# STM32H743VGT6.net
KiCad netlist of a schematic drawn in Altium Designer
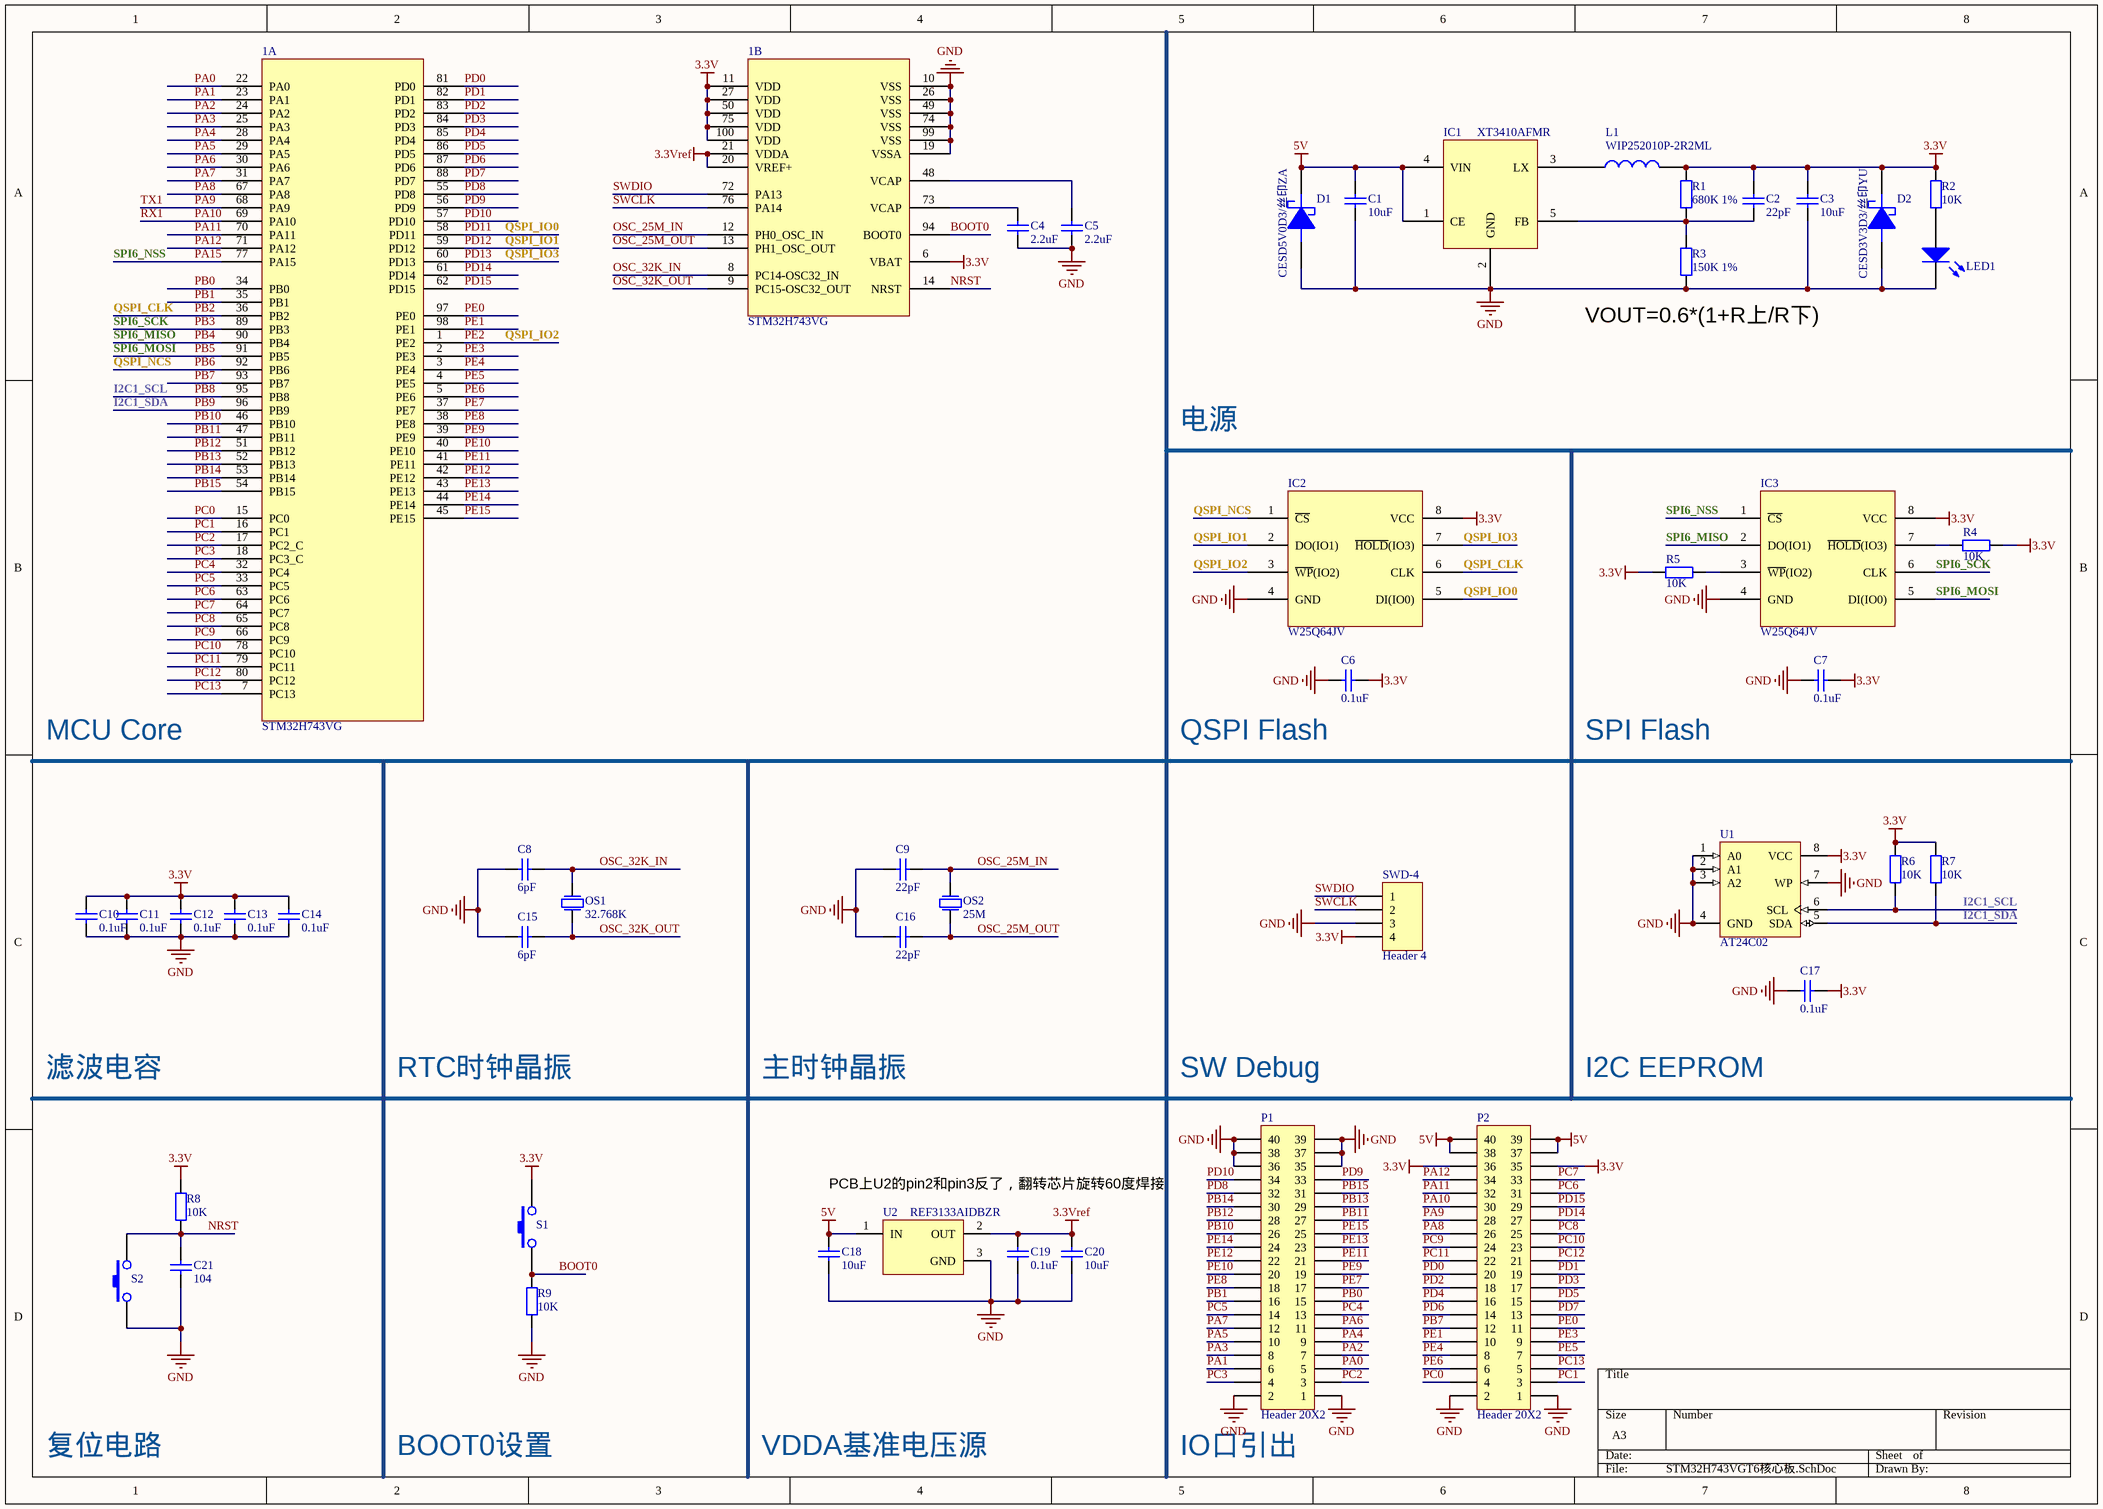
[diagram p0: STM32H743VGT6核心板.SchDoc]

(export (version "E")
  (design (tool "Eeschema 10.0.6"))
  (components
    (comp (ref "1")
      (value "STM32H743VG")
      (footprint "F-QFP14x14-G100/P.5N")
      (libsource (lib "反客STM32H743VGT6核心板零散元件") (part "STM32H743VG"))
    )
    (comp (ref "C1")
      (value "10uF")
      (footprint "C 0603_M")
      (libsource (lib "反客STM32H743VGT6核心板零散元件") (part "Cap1_3"))
    )
    (comp (ref "C2")
      (value "22pF")
      (footprint "C 0603_M")
      (libsource (lib "反客STM32H743VGT6核心板零散元件") (part "Cap1_1"))
    )
    (comp (ref "C3")
      (value "10uF")
      (footprint "C 0603_M")
      (libsource (lib "反客STM32H743VGT6核心板零散元件") (part "Cap1_3"))
    )
    (comp (ref "C4")
      (value "2.2uF")
      (footprint "C 0603_M")
      (libsource (lib "反客STM32H743VGT6核心板零散元件") (part "Cap1_4"))
    )
    (comp (ref "C5")
      (value "2.2uF")
      (footprint "C 0603_M")
      (libsource (lib "反客STM32H743VGT6核心板零散元件") (part "Cap1_4"))
    )
    (comp (ref "C6")
      (value "0.1uF")
      (footprint "C 0603_M")
      (libsource (lib "反客STM32H743VGT6核心板零散元件") (part "Cap1"))
    )
    (comp (ref "C7")
      (value "0.1uF")
      (footprint "C 0603_M")
      (libsource (lib "反客STM32H743VGT6核心板零散元件") (part "Cap1"))
    )
    (comp (ref "C8") (value "6pF") (footprint "C 0603_M") (libsource (lib "零散元件库") (part "Cap1")))
    (comp (ref "C9") (value "22pF") (footprint "C 0603_M") (libsource (lib "零散元件库") (part "Cap1")))
    (comp (ref "C10")
      (value "0.1uF")
      (footprint "C 0603_M")
      (libsource (lib "反客STM32H743VGT6核心板零散元件") (part "Cap1"))
    )
    (comp (ref "C11")
      (value "0.1uF")
      (footprint "C 0603_M")
      (libsource (lib "反客STM32H743VGT6核心板零散元件") (part "Cap1"))
    )
    (comp (ref "C12")
      (value "0.1uF")
      (footprint "C 0603_M")
      (libsource (lib "反客STM32H743VGT6核心板零散元件") (part "Cap1"))
    )
    (comp (ref "C13")
      (value "0.1uF")
      (footprint "C 0603_M")
      (libsource (lib "反客STM32H743VGT6核心板零散元件") (part "Cap1"))
    )
    (comp (ref "C14")
      (value "0.1uF")
      (footprint "C 0603_M")
      (libsource (lib "反客STM32H743VGT6核心板零散元件") (part "Cap1"))
    )
    (comp (ref "C15") (value "6pF") (footprint "C 0603_M") (libsource (lib "零散元件库") (part "Cap1")))
    (comp (ref "C16") (value "22pF") (footprint "C 0603_M") (libsource (lib "零散元件库") (part "Cap1")))
    (comp (ref "C17")
      (value "0.1uF")
      (footprint "C 0603_M")
      (libsource (lib "反客STM32H743VGT6核心板零散元件") (part "Cap1"))
    )
    (comp (ref "C18")
      (value "10uF")
      (footprint "C 0603_M")
      (libsource (lib "反客STM32H743VGT6核心板零散元件") (part "Cap1_3"))
    )
    (comp (ref "C19")
      (value "0.1uF")
      (footprint "C 0603_M")
      (libsource (lib "反客STM32H743VGT6核心板零散元件") (part "Cap1"))
    )
    (comp (ref "C20")
      (value "10uF")
      (footprint "C 0603_M")
      (libsource (lib "反客STM32H743VGT6核心板零散元件") (part "Cap1_3"))
    )
    (comp (ref "C21") (value "104") (footprint "C 0603_M") (libsource (lib "零散元件库") (part "Cap1")))
    (comp (ref "D1")
      (value "CESD5V0D3/丝印ZA")
      (footprint "SOD323")
      (libsource (lib "反客STM32H743VGT6核心板零散元件") (part "TVS"))
    )
    (comp (ref "D2")
      (value "CESD3V3D3/丝印YU")
      (footprint "SOD323")
      (libsource (lib "反客STM32H743VGT6核心板零散元件") (part "TVS_1"))
    )
    (comp (ref "IC1")
      (value "XT3410AFMR")
      (footprint "SOT23-5P")
      (libsource (lib "反客STM32H743VGT6核心板零散元件") (part "XT3410AFMR"))
    )
    (comp (ref "IC2")
      (value "W25Q64JV")
      (footprint "SOIC-W-8")
      (libsource (lib "反客STM32H743VGT6核心板零散元件") (part "W25QXX_FLASH"))
    )
    (comp (ref "IC3")
      (value "W25Q64JV")
      (footprint "SOIC-W-8")
      (libsource (lib "反客STM32H743VGT6核心板零散元件") (part "W25QXX_FLASH"))
    )
    (comp (ref "L1")
      (value "WIP252010P-2R2ML")
      (footprint "电感2520X10N")
      (libsource (lib "反客STM32H743VGT6核心板零散元件") (part "电感_1"))
    )
    (comp (ref "LED1")
      (value "LED")
      (footprint "LED 0603W")
      (libsource (lib "反客STM32H743VGT6核心板零散元件") (part "LED"))
    )
    (comp (ref "OS1")
      (value "32.768K")
      (footprint "R 0805_M")
      (fields (field (name "VAULE") "32.768K"))
      (libsource (lib "零散元件库") (part "晶振"))
    )
    (comp (ref "OS2")
      (value "25M")
      (footprint "3225")
      (fields (field (name "VAULE") "25M"))
      (libsource (lib "反客STM32H743VGT6核心板零散元件") (part "晶振"))
    )
    (comp (ref "P1")
      (value "Header 20X2")
      (footprint "HDR-SMD_40P-P1.27-V-M-R2-C20-LS5.3")
      (description "Header, 20-Pin, Dual row")
      (fields (field (name "PUBLISHER") "Altium Limited"))
      (libsource (lib "反客STM32H743VGT6核心板零散元件") (part "Header 20X2"))
    )
    (comp (ref "P2")
      (value "Header 20X2")
      (footprint "HDR-SMD_40P-P1.27-V-M-R2-C20-LS5.3")
      (description "Header, 20-Pin, Dual row")
      (fields (field (name "PUBLISHER") "Altium Limited"))
      (libsource (lib "反客STM32H743VGT6核心板零散元件") (part "Header 20X2"))
    )
    (comp (ref "R1")
      (value "680K 1%")
      (footprint "R 0603_M")
      (libsource (lib "反客STM32H743VGT6核心板零散元件") (part "Res_5"))
    )
    (comp (ref "R2")
      (value "10K")
      (footprint "R 0603_M")
      (libsource (lib "反客STM32H743VGT6核心板零散元件") (part "Res"))
    )
    (comp (ref "R3")
      (value "150K 1%")
      (footprint "R 0603_M")
      (libsource (lib "反客STM32H743VGT6核心板零散元件") (part "Res_6"))
    )
    (comp (ref "R4")
      (value "10K")
      (footprint "R 0603_M")
      (libsource (lib "反客STM32H743VGT6核心板零散元件") (part "Res_1"))
    )
    (comp (ref "R5")
      (value "10K")
      (footprint "R 0603_M")
      (libsource (lib "反客STM32H743VGT6核心板零散元件") (part "Res_1"))
    )
    (comp (ref "R6") (value "10K") (footprint "R 0603_M") (libsource (lib "") (part "Res_1_1")))
    (comp (ref "R7") (value "10K") (footprint "R 0603_M") (libsource (lib "") (part "Res_1_1")))
    (comp (ref "R8") (value "10K") (footprint "R 0603_M") (libsource (lib "零散元件库") (part "Res")))
    (comp (ref "R9") (value "10K") (footprint "R 0603_M") (libsource (lib "零散元件库") (part "Res")))
    (comp (ref "S1") (value "KEY") (footprint "SWT3*4") (libsource (lib "CCDXPLIB") (part "KEY")))
    (comp (ref "S2") (value "KEY") (footprint "SWT3*4") (libsource (lib "CCDXPLIB") (part "KEY")))
    (comp (ref "SWD-4")
      (value "Header 4")
      (footprint "PH2.0-WI-4P")
      (description "Header, 4-Pin")
      (fields (field (name "PUBLISHER") "Altium Limited"))
      (libsource (lib "Miscellaneous Connectors") (part "Header 4"))
    )
    (comp (ref "U1")
      (value "AT24C02")
      (footprint "8S1_N")
      (libsource (lib "Atmel Serial EEPROM") (part "AT24C02BN-SP25-B"))
    )
    (comp (ref "U2")
      (value "REF3133AIDBZR")
      (footprint "SOT23")
      (fields (field (name "MANUFACTURER") "Texas Instruments"))
      (libsource (lib "TI Power Management Series Voltage Reference") (part "REF3133AIDBZR"))
    )
  )
  (nets
    (net (code "1") (name "/BOOT0") (class "Default")
      (node (ref "1") (pin "94") (pinfunction "BOOT0_94") (pintype "passive"))
      (node (ref "R9") (pin "2") (pinfunction "2_2") (pintype "passive"))
      (node (ref "S1") (pin "1") (pinfunction "1_1") (pintype "passive"))
    )
    (net (code "2") (name "/I2C1_SCL") (class "Default")
      (node (ref "1") (pin "95") (pinfunction "PB8_95") (pintype "passive"))
      (node (ref "R6") (pin "1") (pinfunction "1_1") (pintype "passive"))
      (node (ref "U1") (pin "6") (pinfunction "SCL_6") (pintype "input"))
    )
    (net (code "3") (name "/I2C1_SDA") (class "Default")
      (node (ref "1") (pin "96") (pinfunction "PB9_96") (pintype "passive"))
      (node (ref "R7") (pin "1") (pinfunction "1_1") (pintype "passive"))
      (node (ref "U1") (pin "5") (pinfunction "SDA_5") (pintype "bidirectional"))
    )
    (net (code "4") (name "/NRST") (class "Default")
      (node (ref "1") (pin "14") (pinfunction "NRST_14") (pintype "passive"))
      (node (ref "C21") (pin "2") (pinfunction "2_2") (pintype "passive"))
      (node (ref "R8") (pin "1") (pinfunction "1_1") (pintype "passive"))
      (node (ref "S2") (pin "2") (pinfunction "2_2") (pintype "passive"))
    )
    (net (code "5") (name "/OSC_25M_IN") (class "Default")
      (node (ref "1") (pin "12") (pinfunction "PH0_OSC_IN_12") (pintype "passive"))
      (node (ref "C9") (pin "1") (pinfunction "1_1") (pintype "passive"))
      (node (ref "OS2") (pin "1") (pinfunction "P1_1") (pintype "passive"))
    )
    (net (code "6") (name "/OSC_25M_OUT") (class "Default")
      (node (ref "1") (pin "13") (pinfunction "PH1_OSC_OUT_13") (pintype "passive"))
      (node (ref "C16") (pin "1") (pinfunction "1_1") (pintype "passive"))
      (node (ref "OS2") (pin "2") (pinfunction "P2_2") (pintype "passive"))
    )
    (net (code "7") (name "/OSC_32K_IN") (class "Default")
      (node (ref "1") (pin "8") (pinfunction "PC14-OSC32_IN_8") (pintype "passive"))
      (node (ref "C8") (pin "1") (pinfunction "1_1") (pintype "passive"))
      (node (ref "OS1") (pin "1") (pinfunction "P1_1") (pintype "passive"))
    )
    (net (code "8") (name "/OSC_32K_OUT") (class "Default")
      (node (ref "1") (pin "9") (pinfunction "PC15-OSC32_OUT_9") (pintype "passive"))
      (node (ref "C15") (pin "1") (pinfunction "1_1") (pintype "passive"))
      (node (ref "OS1") (pin "2") (pinfunction "P2_2") (pintype "passive"))
    )
    (net (code "9") (name "/PA0") (class "Default")
      (node (ref "1") (pin "22") (pinfunction "PA0_22") (pintype "passive"))
      (node (ref "P1") (pin "5") (pinfunction "5_5") (pintype "passive"))
    )
    (net (code "10") (name "/PA1") (class "Default")
      (node (ref "1") (pin "23") (pinfunction "PA1_23") (pintype "passive"))
      (node (ref "P1") (pin "6") (pinfunction "6_6") (pintype "passive"))
    )
    (net (code "11") (name "/PA2") (class "Default")
      (node (ref "1") (pin "24") (pinfunction "PA2_24") (pintype "passive"))
      (node (ref "P1") (pin "7") (pinfunction "7_7") (pintype "passive"))
    )
    (net (code "12") (name "/PA3") (class "Default")
      (node (ref "1") (pin "25") (pinfunction "PA3_25") (pintype "passive"))
      (node (ref "P1") (pin "8") (pinfunction "8_8") (pintype "passive"))
    )
    (net (code "13") (name "/PA4") (class "Default")
      (node (ref "1") (pin "28") (pinfunction "PA4_28") (pintype "passive"))
      (node (ref "P1") (pin "9") (pinfunction "9_9") (pintype "passive"))
    )
    (net (code "14") (name "/PA5") (class "Default")
      (node (ref "1") (pin "29") (pinfunction "PA5_29") (pintype "passive"))
      (node (ref "P1") (pin "10") (pinfunction "10_10") (pintype "passive"))
    )
    (net (code "15") (name "/PA6") (class "Default")
      (node (ref "1") (pin "30") (pinfunction "PA6_30") (pintype "passive"))
      (node (ref "P1") (pin "11") (pinfunction "11_11") (pintype "passive"))
    )
    (net (code "16") (name "/PA7") (class "Default")
      (node (ref "1") (pin "31") (pinfunction "PA7_31") (pintype "passive"))
      (node (ref "P1") (pin "12") (pinfunction "12_12") (pintype "passive"))
    )
    (net (code "17") (name "/PA8") (class "Default")
      (node (ref "1") (pin "67") (pinfunction "PA8_67") (pintype "passive"))
      (node (ref "P2") (pin "26") (pinfunction "26_26") (pintype "passive"))
    )
    (net (code "18") (name "/PA9") (class "Default")
      (node (ref "1") (pin "68") (pinfunction "PA9_68") (pintype "passive"))
      (node (ref "P2") (pin "28") (pinfunction "28_28") (pintype "passive"))
    )
    (net (code "19") (name "/PA10") (class "Default")
      (node (ref "1") (pin "69") (pinfunction "PA10_69") (pintype "passive"))
      (node (ref "P2") (pin "30") (pinfunction "30_30") (pintype "passive"))
    )
    (net (code "20") (name "/PA11") (class "Default")
      (node (ref "1") (pin "70") (pinfunction "PA11_70") (pintype "passive"))
      (node (ref "P2") (pin "32") (pinfunction "32_32") (pintype "passive"))
    )
    (net (code "21") (name "/PA12") (class "Default")
      (node (ref "1") (pin "71") (pinfunction "PA12_71") (pintype "passive"))
      (node (ref "P2") (pin "34") (pinfunction "34_34") (pintype "passive"))
    )
    (net (code "22") (name "/PA15") (class "Default")
      (node (ref "1") (pin "77") (pinfunction "PA15_77") (pintype "passive"))
      (node (ref "IC3") (pin "1") (pinfunction "~{CS}_1") (pintype "passive"))
    )
    (net (code "23") (name "/PB0") (class "Default")
      (node (ref "1") (pin "34") (pinfunction "PB0_34") (pintype "passive"))
      (node (ref "P1") (pin "15") (pinfunction "15_15") (pintype "passive"))
    )
    (net (code "24") (name "/PB1") (class "Default")
      (node (ref "1") (pin "35") (pinfunction "PB1_35") (pintype "passive"))
      (node (ref "P1") (pin "16") (pinfunction "16_16") (pintype "passive"))
    )
    (net (code "25") (name "/PB2") (class "Default")
      (node (ref "1") (pin "36") (pinfunction "PB2_36") (pintype "passive"))
      (node (ref "IC2") (pin "6") (pinfunction "CLK_6") (pintype "passive"))
    )
    (net (code "26") (name "/PB3") (class "Default")
      (node (ref "1") (pin "89") (pinfunction "PB3_89") (pintype "passive"))
      (node (ref "IC3") (pin "6") (pinfunction "CLK_6") (pintype "passive"))
    )
    (net (code "27") (name "/PB4") (class "Default")
      (node (ref "1") (pin "90") (pinfunction "PB4_90") (pintype "passive"))
      (node (ref "IC3") (pin "2") (pinfunction "DO(IO1)_2") (pintype "passive"))
    )
    (net (code "28") (name "/PB5") (class "Default")
      (node (ref "1") (pin "91") (pinfunction "PB5_91") (pintype "passive"))
      (node (ref "IC3") (pin "5") (pinfunction "DI(IO0)_5") (pintype "passive"))
    )
    (net (code "29") (name "/PB6") (class "Default")
      (node (ref "1") (pin "92") (pinfunction "PB6_92") (pintype "passive"))
      (node (ref "IC2") (pin "1") (pinfunction "~{CS}_1") (pintype "passive"))
    )
    (net (code "30") (name "/PB7") (class "Default")
      (node (ref "1") (pin "93") (pinfunction "PB7_93") (pintype "passive"))
      (node (ref "P2") (pin "12") (pinfunction "12_12") (pintype "passive"))
    )
    (net (code "31") (name "/PB10") (class "Default")
      (node (ref "1") (pin "46") (pinfunction "PB10_46") (pintype "passive"))
      (node (ref "P1") (pin "26") (pinfunction "26_26") (pintype "passive"))
    )
    (net (code "32") (name "/PB11") (class "Default")
      (node (ref "1") (pin "47") (pinfunction "PB11_47") (pintype "passive"))
      (node (ref "P1") (pin "27") (pinfunction "27_27") (pintype "passive"))
    )
    (net (code "33") (name "/PB12") (class "Default")
      (node (ref "1") (pin "51") (pinfunction "PB12_51") (pintype "passive"))
      (node (ref "P1") (pin "28") (pinfunction "28_28") (pintype "passive"))
    )
    (net (code "34") (name "/PB13") (class "Default")
      (node (ref "1") (pin "52") (pinfunction "PB13_52") (pintype "passive"))
      (node (ref "P1") (pin "29") (pinfunction "29_29") (pintype "passive"))
    )
    (net (code "35") (name "/PB14") (class "Default")
      (node (ref "1") (pin "53") (pinfunction "PB14_53") (pintype "passive"))
      (node (ref "P1") (pin "30") (pinfunction "30_30") (pintype "passive"))
    )
    (net (code "36") (name "/PB15") (class "Default")
      (node (ref "1") (pin "54") (pinfunction "PB15_54") (pintype "passive"))
      (node (ref "P1") (pin "31") (pinfunction "31_31") (pintype "passive"))
    )
    (net (code "37") (name "/PC0") (class "Default")
      (node (ref "1") (pin "15") (pinfunction "PC0_15") (pintype "passive"))
      (node (ref "P2") (pin "4") (pinfunction "4_4") (pintype "passive"))
    )
    (net (code "38") (name "/PC1") (class "Default")
      (node (ref "1") (pin "16") (pinfunction "PC1_16") (pintype "passive"))
      (node (ref "P2") (pin "3") (pinfunction "3_3") (pintype "passive"))
    )
    (net (code "39") (name "/PC2") (class "Default")
      (node (ref "1") (pin "17") (pinfunction "PC2_C_17") (pintype "passive"))
      (node (ref "P1") (pin "3") (pinfunction "3_3") (pintype "passive"))
    )
    (net (code "40") (name "/PC3") (class "Default")
      (node (ref "1") (pin "18") (pinfunction "PC3_C_18") (pintype "passive"))
      (node (ref "P1") (pin "4") (pinfunction "4_4") (pintype "passive"))
    )
    (net (code "41") (name "/PC4") (class "Default")
      (node (ref "1") (pin "32") (pinfunction "PC4_32") (pintype "passive"))
      (node (ref "P1") (pin "13") (pinfunction "13_13") (pintype "passive"))
    )
    (net (code "42") (name "/PC5") (class "Default")
      (node (ref "1") (pin "33") (pinfunction "PC5_33") (pintype "passive"))
      (node (ref "P1") (pin "14") (pinfunction "14_14") (pintype "passive"))
    )
    (net (code "43") (name "/PC6") (class "Default")
      (node (ref "1") (pin "63") (pinfunction "PC6_63") (pintype "passive"))
      (node (ref "P2") (pin "31") (pinfunction "31_31") (pintype "passive"))
    )
    (net (code "44") (name "/PC7") (class "Default")
      (node (ref "1") (pin "64") (pinfunction "PC7_64") (pintype "passive"))
      (node (ref "P2") (pin "33") (pinfunction "33_33") (pintype "passive"))
    )
    (net (code "45") (name "/PC8") (class "Default")
      (node (ref "1") (pin "65") (pinfunction "PC8_65") (pintype "passive"))
      (node (ref "P2") (pin "25") (pinfunction "25_25") (pintype "passive"))
    )
    (net (code "46") (name "/PC9") (class "Default")
      (node (ref "1") (pin "66") (pinfunction "PC9_66") (pintype "passive"))
      (node (ref "P2") (pin "24") (pinfunction "24_24") (pintype "passive"))
    )
    (net (code "47") (name "/PC10") (class "Default")
      (node (ref "1") (pin "78") (pinfunction "PC10_78") (pintype "passive"))
      (node (ref "P2") (pin "23") (pinfunction "23_23") (pintype "passive"))
    )
    (net (code "48") (name "/PC11") (class "Default")
      (node (ref "1") (pin "79") (pinfunction "PC11_79") (pintype "passive"))
      (node (ref "P2") (pin "22") (pinfunction "22_22") (pintype "passive"))
    )
    (net (code "49") (name "/PC12") (class "Default")
      (node (ref "1") (pin "80") (pinfunction "PC12_80") (pintype "passive"))
      (node (ref "P2") (pin "21") (pinfunction "21_21") (pintype "passive"))
    )
    (net (code "50") (name "/PC13") (class "Default")
      (node (ref "1") (pin "7") (pinfunction "PC13_7") (pintype "passive"))
      (node (ref "P2") (pin "5") (pinfunction "5_5") (pintype "passive"))
    )
    (net (code "51") (name "/PD0") (class "Default")
      (node (ref "1") (pin "81") (pinfunction "PD0_81") (pintype "passive"))
      (node (ref "P2") (pin "20") (pinfunction "20_20") (pintype "passive"))
    )
    (net (code "52") (name "/PD1") (class "Default")
      (node (ref "1") (pin "82") (pinfunction "PD1_82") (pintype "passive"))
      (node (ref "P2") (pin "19") (pinfunction "19_19") (pintype "passive"))
    )
    (net (code "53") (name "/PD2") (class "Default")
      (node (ref "1") (pin "83") (pinfunction "PD2_83") (pintype "passive"))
      (node (ref "P2") (pin "18") (pinfunction "18_18") (pintype "passive"))
    )
    (net (code "54") (name "/PD3") (class "Default")
      (node (ref "1") (pin "84") (pinfunction "PD3_84") (pintype "passive"))
      (node (ref "P2") (pin "17") (pinfunction "17_17") (pintype "passive"))
    )
    (net (code "55") (name "/PD4") (class "Default")
      (node (ref "1") (pin "85") (pinfunction "PD4_85") (pintype "passive"))
      (node (ref "P2") (pin "16") (pinfunction "16_16") (pintype "passive"))
    )
    (net (code "56") (name "/PD5") (class "Default")
      (node (ref "1") (pin "86") (pinfunction "PD5_86") (pintype "passive"))
      (node (ref "P2") (pin "15") (pinfunction "15_15") (pintype "passive"))
    )
    (net (code "57") (name "/PD6") (class "Default")
      (node (ref "1") (pin "87") (pinfunction "PD6_87") (pintype "passive"))
      (node (ref "P2") (pin "14") (pinfunction "14_14") (pintype "passive"))
    )
    (net (code "58") (name "/PD7") (class "Default")
      (node (ref "1") (pin "88") (pinfunction "PD7_88") (pintype "passive"))
      (node (ref "P2") (pin "13") (pinfunction "13_13") (pintype "passive"))
    )
    (net (code "59") (name "/PD8") (class "Default")
      (node (ref "1") (pin "55") (pinfunction "PD8_55") (pintype "passive"))
      (node (ref "P1") (pin "32") (pinfunction "32_32") (pintype "passive"))
    )
    (net (code "60") (name "/PD9") (class "Default")
      (node (ref "1") (pin "56") (pinfunction "PD9_56") (pintype "passive"))
      (node (ref "P1") (pin "33") (pinfunction "33_33") (pintype "passive"))
    )
    (net (code "61") (name "/PD10") (class "Default")
      (node (ref "1") (pin "57") (pinfunction "PD10_57") (pintype "passive"))
      (node (ref "P1") (pin "34") (pinfunction "34_34") (pintype "passive"))
    )
    (net (code "62") (name "/PD11") (class "Default")
      (node (ref "1") (pin "58") (pinfunction "PD11_58") (pintype "passive"))
      (node (ref "IC2") (pin "5") (pinfunction "DI(IO0)_5") (pintype "passive"))
    )
    (net (code "63") (name "/PD12") (class "Default")
      (node (ref "1") (pin "59") (pinfunction "PD12_59") (pintype "passive"))
      (node (ref "IC2") (pin "2") (pinfunction "DO(IO1)_2") (pintype "passive"))
    )
    (net (code "64") (name "/PD13") (class "Default")
      (node (ref "1") (pin "60") (pinfunction "PD13_60") (pintype "passive"))
      (node (ref "IC2") (pin "7") (pinfunction "~{HOLD}(IO3)_7") (pintype "passive"))
    )
    (net (code "65") (name "/PD14") (class "Default")
      (node (ref "1") (pin "61") (pinfunction "PD14_61") (pintype "passive"))
      (node (ref "P2") (pin "27") (pinfunction "27_27") (pintype "passive"))
    )
    (net (code "66") (name "/PD15") (class "Default")
      (node (ref "1") (pin "62") (pinfunction "PD15_62") (pintype "passive"))
      (node (ref "P2") (pin "29") (pinfunction "29_29") (pintype "passive"))
    )
    (net (code "67") (name "/PE0") (class "Default")
      (node (ref "1") (pin "97") (pinfunction "PE0_97") (pintype "passive"))
      (node (ref "P2") (pin "11") (pinfunction "11_11") (pintype "passive"))
    )
    (net (code "68") (name "/PE1") (class "Default")
      (node (ref "1") (pin "98") (pinfunction "PE1_98") (pintype "passive"))
      (node (ref "P2") (pin "10") (pinfunction "10_10") (pintype "passive"))
    )
    (net (code "69") (name "/PE2") (class "Default")
      (node (ref "1") (pin "1") (pinfunction "PE2_1") (pintype "passive"))
      (node (ref "IC2") (pin "3") (pinfunction "~{WP}(IO2)_3") (pintype "passive"))
    )
    (net (code "70") (name "/PE3") (class "Default")
      (node (ref "1") (pin "2") (pinfunction "PE3_2") (pintype "passive"))
      (node (ref "P2") (pin "9") (pinfunction "9_9") (pintype "passive"))
    )
    (net (code "71") (name "/PE4") (class "Default")
      (node (ref "1") (pin "3") (pinfunction "PE4_3") (pintype "passive"))
      (node (ref "P2") (pin "8") (pinfunction "8_8") (pintype "passive"))
    )
    (net (code "72") (name "/PE5") (class "Default")
      (node (ref "1") (pin "4") (pinfunction "PE5_4") (pintype "passive"))
      (node (ref "P2") (pin "7") (pinfunction "7_7") (pintype "passive"))
    )
    (net (code "73") (name "/PE6") (class "Default")
      (node (ref "1") (pin "5") (pinfunction "PE6_5") (pintype "passive"))
      (node (ref "P2") (pin "6") (pinfunction "6_6") (pintype "passive"))
    )
    (net (code "74") (name "/PE7") (class "Default")
      (node (ref "1") (pin "37") (pinfunction "PE7_37") (pintype "passive"))
      (node (ref "P1") (pin "17") (pinfunction "17_17") (pintype "passive"))
    )
    (net (code "75") (name "/PE8") (class "Default")
      (node (ref "1") (pin "38") (pinfunction "PE8_38") (pintype "passive"))
      (node (ref "P1") (pin "18") (pinfunction "18_18") (pintype "passive"))
    )
    (net (code "76") (name "/PE9") (class "Default")
      (node (ref "1") (pin "39") (pinfunction "PE9_39") (pintype "passive"))
      (node (ref "P1") (pin "19") (pinfunction "19_19") (pintype "passive"))
    )
    (net (code "77") (name "/PE10") (class "Default")
      (node (ref "1") (pin "40") (pinfunction "PE10_40") (pintype "passive"))
      (node (ref "P1") (pin "20") (pinfunction "20_20") (pintype "passive"))
    )
    (net (code "78") (name "/PE11") (class "Default")
      (node (ref "1") (pin "41") (pinfunction "PE11_41") (pintype "passive"))
      (node (ref "P1") (pin "21") (pinfunction "21_21") (pintype "passive"))
    )
    (net (code "79") (name "/PE12") (class "Default")
      (node (ref "1") (pin "42") (pinfunction "PE12_42") (pintype "passive"))
      (node (ref "P1") (pin "22") (pinfunction "22_22") (pintype "passive"))
    )
    (net (code "80") (name "/PE13") (class "Default")
      (node (ref "1") (pin "43") (pinfunction "PE13_43") (pintype "passive"))
      (node (ref "P1") (pin "23") (pinfunction "23_23") (pintype "passive"))
    )
    (net (code "81") (name "/PE14") (class "Default")
      (node (ref "1") (pin "44") (pinfunction "PE14_44") (pintype "passive"))
      (node (ref "P1") (pin "24") (pinfunction "24_24") (pintype "passive"))
    )
    (net (code "82") (name "/PE15") (class "Default")
      (node (ref "1") (pin "45") (pinfunction "PE15_45") (pintype "passive"))
      (node (ref "P1") (pin "25") (pinfunction "25_25") (pintype "passive"))
    )
    (net (code "83") (name "/SWCLK") (class "Default")
      (node (ref "1") (pin "76") (pinfunction "PA14_76") (pintype "passive"))
      (node (ref "SWD-4") (pin "2") (pinfunction "2_2") (pintype "passive"))
    )
    (net (code "84") (name "/SWDIO") (class "Default")
      (node (ref "1") (pin "72") (pinfunction "PA13_72") (pintype "passive"))
      (node (ref "SWD-4") (pin "1") (pinfunction "1_1") (pintype "passive"))
    )
    (net (code "85") (name "3.3V") (class "Default")
      (node (ref "1") (pin "100") (pinfunction "VDD_100") (pintype "passive"))
      (node (ref "1") (pin "11") (pinfunction "VDD_11") (pintype "passive"))
      (node (ref "1") (pin "27") (pinfunction "VDD_27") (pintype "passive"))
      (node (ref "1") (pin "50") (pinfunction "VDD_50") (pintype "passive"))
      (node (ref "1") (pin "6") (pinfunction "VBAT_6") (pintype "passive"))
      (node (ref "1") (pin "75") (pinfunction "VDD_75") (pintype "passive"))
      (node (ref "C10") (pin "2") (pinfunction "2_2") (pintype "passive"))
      (node (ref "C11") (pin "2") (pinfunction "2_2") (pintype "passive"))
      (node (ref "C12") (pin "2") (pinfunction "2_2") (pintype "passive"))
      (node (ref "C13") (pin "2") (pinfunction "2_2") (pintype "passive"))
      (node (ref "C14") (pin "2") (pinfunction "2_2") (pintype "passive"))
      (node (ref "C17") (pin "2") (pinfunction "2_2") (pintype "passive"))
      (node (ref "C2") (pin "2") (pinfunction "2_2") (pintype "passive"))
      (node (ref "C3") (pin "2") (pinfunction "2_2") (pintype "passive"))
      (node (ref "C6") (pin "2") (pinfunction "2_2") (pintype "passive"))
      (node (ref "C7") (pin "2") (pinfunction "2_2") (pintype "passive"))
      (node (ref "D2") (pin "2") (pinfunction "-_2") (pintype "passive"))
      (node (ref "IC2") (pin "8") (pinfunction "VCC_8") (pintype "passive"))
      (node (ref "IC3") (pin "8") (pinfunction "VCC_8") (pintype "passive"))
      (node (ref "L1") (pin "2") (pinfunction "2_2") (pintype "passive"))
      (node (ref "P2") (pin "35") (pinfunction "35_35") (pintype "passive"))
      (node (ref "P2") (pin "36") (pinfunction "36_36") (pintype "passive"))
      (node (ref "R1") (pin "2") (pinfunction "2_2") (pintype "passive"))
      (node (ref "R2") (pin "1") (pinfunction "1_1") (pintype "passive"))
      (node (ref "R4") (pin "2") (pinfunction "2_2") (pintype "passive"))
      (node (ref "R5") (pin "1") (pinfunction "1_1") (pintype "passive"))
      (node (ref "R6") (pin "2") (pinfunction "2_2") (pintype "passive"))
      (node (ref "R7") (pin "2") (pinfunction "2_2") (pintype "passive"))
      (node (ref "R8") (pin "2") (pinfunction "2_2") (pintype "passive"))
      (node (ref "S1") (pin "2") (pinfunction "2_2") (pintype "passive"))
      (node (ref "SWD-4") (pin "4") (pinfunction "4_4") (pintype "passive"))
      (node (ref "U1") (pin "8") (pinfunction "VCC_8") (pintype "power_in"))
    )
    (net (code "86") (name "3.3Vref") (class "Default")
      (node (ref "1") (pin "20") (pinfunction "VREF+_20") (pintype "passive"))
      (node (ref "1") (pin "21") (pinfunction "VDDA_21") (pintype "passive"))
      (node (ref "C19") (pin "2") (pinfunction "2_2") (pintype "passive"))
      (node (ref "C20") (pin "2") (pinfunction "2_2") (pintype "passive"))
      (node (ref "U2") (pin "2") (pinfunction "OUT_2") (pintype "power_in"))
    )
    (net (code "87") (name "5V") (class "Default")
      (node (ref "C1") (pin "2") (pinfunction "2_2") (pintype "passive"))
      (node (ref "C18") (pin "2") (pinfunction "2_2") (pintype "passive"))
      (node (ref "D1") (pin "2") (pinfunction "-_2") (pintype "passive"))
      (node (ref "IC1") (pin "1") (pinfunction "CE_1") (pintype "passive"))
      (node (ref "IC1") (pin "4") (pinfunction "VIN_4") (pintype "passive"))
      (node (ref "P2") (pin "37") (pinfunction "37_37") (pintype "passive"))
      (node (ref "P2") (pin "38") (pinfunction "38_38") (pintype "passive"))
      (node (ref "P2") (pin "39") (pinfunction "39_39") (pintype "passive"))
      (node (ref "P2") (pin "40") (pinfunction "40_40") (pintype "passive"))
      (node (ref "U2") (pin "1") (pinfunction "IN_1") (pintype "power_in"))
    )
    (net (code "88") (name "GND") (class "Default")
      (node (ref "1") (pin "10") (pinfunction "VSS_10") (pintype "passive"))
      (node (ref "1") (pin "19") (pinfunction "VSSA_19") (pintype "passive"))
      (node (ref "1") (pin "26") (pinfunction "VSS_26") (pintype "passive"))
      (node (ref "1") (pin "49") (pinfunction "VSS_49") (pintype "passive"))
      (node (ref "1") (pin "74") (pinfunction "VSS_74") (pintype "passive"))
      (node (ref "1") (pin "99") (pinfunction "VSS_99") (pintype "passive"))
      (node (ref "C1") (pin "1") (pinfunction "1_1") (pintype "passive"))
      (node (ref "C10") (pin "1") (pinfunction "1_1") (pintype "passive"))
      (node (ref "C11") (pin "1") (pinfunction "1_1") (pintype "passive"))
      (node (ref "C12") (pin "1") (pinfunction "1_1") (pintype "passive"))
      (node (ref "C13") (pin "1") (pinfunction "1_1") (pintype "passive"))
      (node (ref "C14") (pin "1") (pinfunction "1_1") (pintype "passive"))
      (node (ref "C15") (pin "2") (pinfunction "2_2") (pintype "passive"))
      (node (ref "C16") (pin "2") (pinfunction "2_2") (pintype "passive"))
      (node (ref "C17") (pin "1") (pinfunction "1_1") (pintype "passive"))
      (node (ref "C18") (pin "1") (pinfunction "1_1") (pintype "passive"))
      (node (ref "C19") (pin "1") (pinfunction "1_1") (pintype "passive"))
      (node (ref "C20") (pin "1") (pinfunction "1_1") (pintype "passive"))
      (node (ref "C21") (pin "1") (pinfunction "1_1") (pintype "passive"))
      (node (ref "C3") (pin "1") (pinfunction "1_1") (pintype "passive"))
      (node (ref "C4") (pin "1") (pinfunction "1_1") (pintype "passive"))
      (node (ref "C5") (pin "1") (pinfunction "1_1") (pintype "passive"))
      (node (ref "C6") (pin "1") (pinfunction "1_1") (pintype "passive"))
      (node (ref "C7") (pin "1") (pinfunction "1_1") (pintype "passive"))
      (node (ref "C8") (pin "2") (pinfunction "2_2") (pintype "passive"))
      (node (ref "C9") (pin "2") (pinfunction "2_2") (pintype "passive"))
      (node (ref "D1") (pin "1") (pinfunction "+_1") (pintype "passive"))
      (node (ref "D2") (pin "1") (pinfunction "+_1") (pintype "passive"))
      (node (ref "IC1") (pin "2") (pinfunction "GND_2") (pintype "passive"))
      (node (ref "IC2") (pin "4") (pinfunction "GND_4") (pintype "passive"))
      (node (ref "IC3") (pin "4") (pinfunction "GND_4") (pintype "passive"))
      (node (ref "LED1") (pin "2") (pinfunction "K_2") (pintype "passive"))
      (node (ref "P1") (pin "1") (pinfunction "1_1") (pintype "passive"))
      (node (ref "P1") (pin "2") (pinfunction "2_2") (pintype "passive"))
      (node (ref "P1") (pin "35") (pinfunction "35_35") (pintype "passive"))
      (node (ref "P1") (pin "36") (pinfunction "36_36") (pintype "passive"))
      (node (ref "P1") (pin "37") (pinfunction "37_37") (pintype "passive"))
      (node (ref "P1") (pin "38") (pinfunction "38_38") (pintype "passive"))
      (node (ref "P1") (pin "39") (pinfunction "39_39") (pintype "passive"))
      (node (ref "P1") (pin "40") (pinfunction "40_40") (pintype "passive"))
      (node (ref "P2") (pin "1") (pinfunction "1_1") (pintype "passive"))
      (node (ref "P2") (pin "2") (pinfunction "2_2") (pintype "passive"))
      (node (ref "R3") (pin "1") (pinfunction "1_1") (pintype "passive"))
      (node (ref "R9") (pin "1") (pinfunction "1_1") (pintype "passive"))
      (node (ref "S2") (pin "1") (pinfunction "1_1") (pintype "passive"))
      (node (ref "SWD-4") (pin "3") (pinfunction "3_3") (pintype "passive"))
      (node (ref "U1") (pin "1") (pinfunction "A0_1") (pintype "input"))
      (node (ref "U1") (pin "2") (pinfunction "A1_2") (pintype "input"))
      (node (ref "U1") (pin "3") (pinfunction "A2_3") (pintype "input"))
      (node (ref "U1") (pin "4") (pinfunction "GND_4") (pintype "power_in"))
      (node (ref "U1") (pin "7") (pinfunction "WP_7") (pintype "input"))
      (node (ref "U2") (pin "3") (pinfunction "GND_3") (pintype "power_in"))
    )
    (net (code "89") (name "Net-(1B-VCAP-Pad48)") (class "Default")
      (node (ref "1") (pin "48") (pinfunction "VCAP_48") (pintype "passive"))
      (node (ref "C5") (pin "2") (pinfunction "2_2") (pintype "passive"))
    )
    (net (code "90") (name "Net-(1B-VCAP-Pad73)") (class "Default")
      (node (ref "1") (pin "73") (pinfunction "VCAP_73") (pintype "passive"))
      (node (ref "C4") (pin "2") (pinfunction "2_2") (pintype "passive"))
    )
    (net (code "91") (name "Net-(IC1-FB)") (class "Default")
      (node (ref "C2") (pin "1") (pinfunction "1_1") (pintype "passive"))
      (node (ref "IC1") (pin "5") (pinfunction "FB_5") (pintype "passive"))
      (node (ref "R1") (pin "1") (pinfunction "1_1") (pintype "passive"))
      (node (ref "R3") (pin "2") (pinfunction "2_2") (pintype "passive"))
    )
    (net (code "92") (name "Net-(IC1-LX)") (class "Default")
      (node (ref "IC1") (pin "3") (pinfunction "LX_3") (pintype "passive"))
      (node (ref "L1") (pin "1") (pinfunction "1_1") (pintype "passive"))
    )
    (net (code "93") (name "Net-(IC3-~{HOLD}(IO3))") (class "Default")
      (node (ref "IC3") (pin "7") (pinfunction "~{HOLD}(IO3)_7") (pintype "passive"))
      (node (ref "R4") (pin "1") (pinfunction "1_1") (pintype "passive"))
    )
    (net (code "94") (name "Net-(IC3-~{WP}(IO2))") (class "Default")
      (node (ref "IC3") (pin "3") (pinfunction "~{WP}(IO2)_3") (pintype "passive"))
      (node (ref "R5") (pin "2") (pinfunction "2_2") (pintype "passive"))
    )
    (net (code "95") (name "Net-(LED1-A)") (class "Default")
      (node (ref "LED1") (pin "1") (pinfunction "A_1") (pintype "passive"))
      (node (ref "R2") (pin "2") (pinfunction "2_2") (pintype "passive"))
    )
  )
)
